# adpd2211_breakout.net
KiCad netlist of a schematic drawn in EAGLE
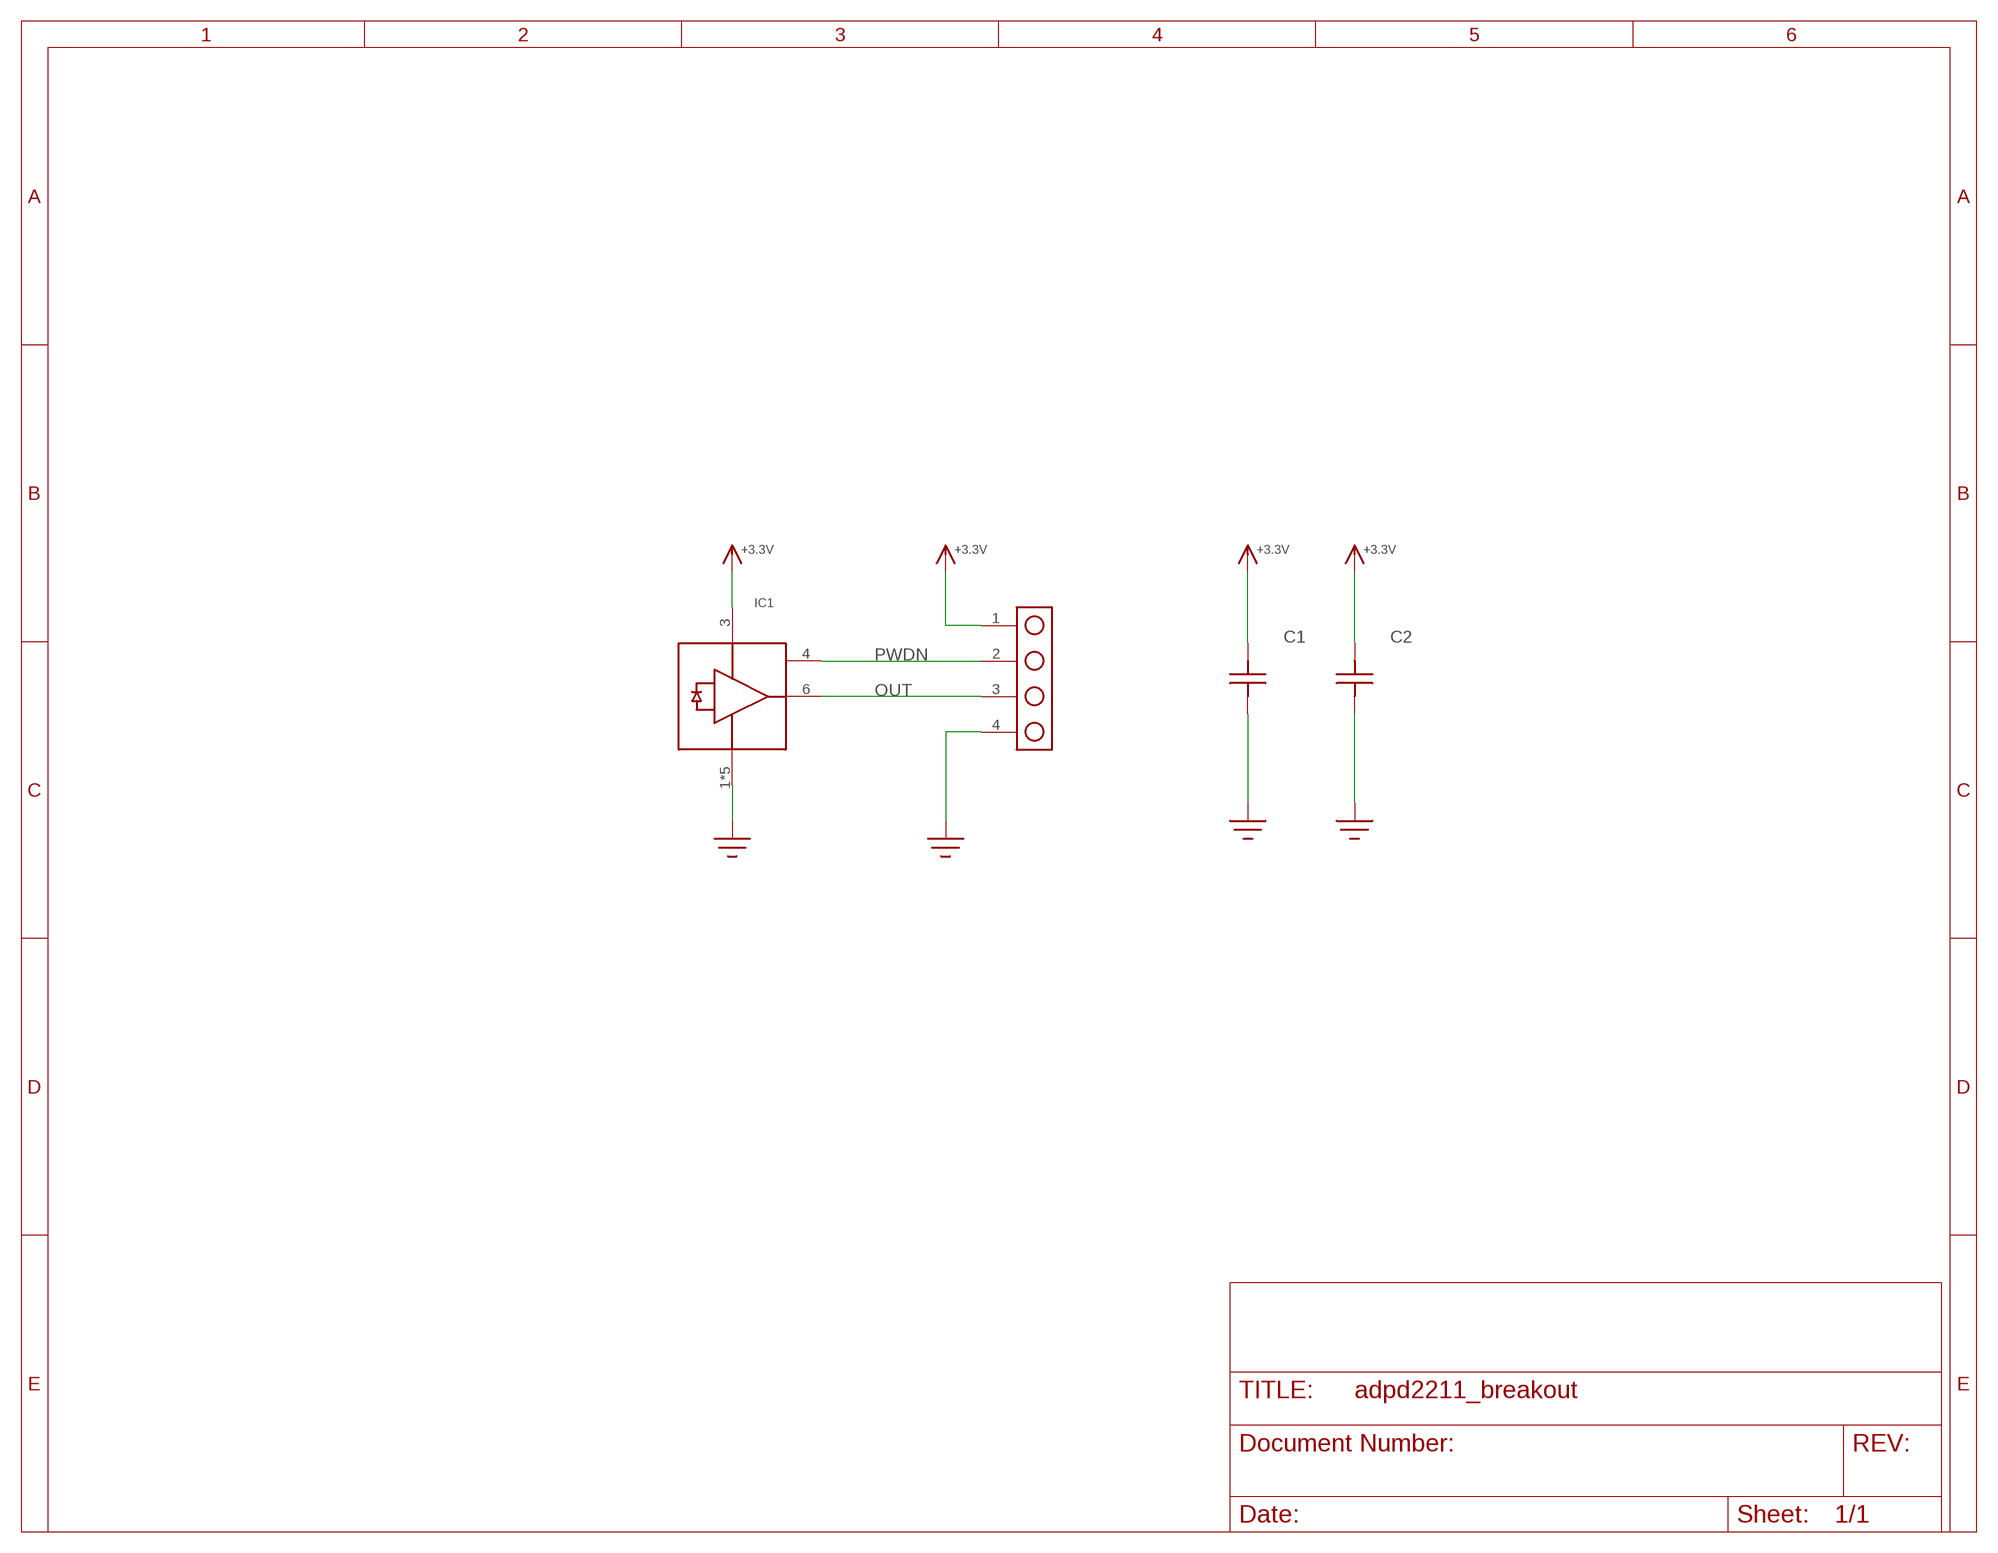
[diagram p0: schematic, sheet 1]

(export (version "E")
  (design (tool "Eeschema 10.0.6"))
  (components
    (comp (ref "C1")
      (value "C0805")
      (footprint "eagle-import:0805")
      (libsource (lib "eagle-import") (part "C0805"))
    )
    (comp (ref "C2")
      (value "C0805")
      (footprint "eagle-import:0805")
      (libsource (lib "eagle-import") (part "C0805"))
    )
    (comp (ref "IC1")
      (value "ADPD2211")
      (footprint "eagle-import:LFCSP8")
      (libsource (lib "eagle-import") (part "ADPD2211"))
    )
    (comp (ref "J1")
      (value "HEADER_4_PIN")
      (footprint "eagle-import:HEADER_4PIN")
      (libsource (lib "eagle-import") (part "HEADER_4_PIN"))
    )
  )
  (nets
    (net (code "1") (name "+3.3V") (class "Default")
      (node (ref "C1") (pin "P$2") (pinfunction "P$2_P$2") (pintype "bidirectional"))
      (node (ref "C2") (pin "P$2") (pinfunction "P$2_P$2") (pintype "bidirectional"))
      (node (ref "IC1") (pin "3") (pinfunction "VCC_3") (pintype "bidirectional"))
      (node (ref "J1") (pin "1") (pinfunction "1_1") (pintype "bidirectional"))
    )
    (net (code "2") (name "/OUT") (class "Default")
      (node (ref "IC1") (pin "6") (pinfunction "OUT_6") (pintype "bidirectional"))
      (node (ref "J1") (pin "3") (pinfunction "3_3") (pintype "bidirectional"))
    )
    (net (code "3") (name "/PWDN") (class "Default")
      (node (ref "IC1") (pin "4") (pinfunction "PWDN_4") (pintype "bidirectional"))
      (node (ref "J1") (pin "2") (pinfunction "2_2") (pintype "bidirectional"))
    )
    (net (code "4") (name "GND") (class "Default")
      (node (ref "C1") (pin "P$1") (pinfunction "P$1_P$1") (pintype "bidirectional"))
      (node (ref "C2") (pin "P$1") (pinfunction "P$1_P$1") (pintype "bidirectional"))
      (node (ref "IC1") (pin "1") (pinfunction "GND_1") (pintype "bidirectional"))
      (node (ref "IC1") (pin "2") (pinfunction "GND_2") (pintype "bidirectional"))
      (node (ref "IC1") (pin "5") (pinfunction "GND_5") (pintype "bidirectional"))
      (node (ref "IC1") (pin "7") (pinfunction "GND_7") (pintype "bidirectional"))
      (node (ref "IC1") (pin "8") (pinfunction "GND_8") (pintype "bidirectional"))
      (node (ref "J1") (pin "4") (pinfunction "4_4") (pintype "bidirectional"))
    )
  )
)
